# 2_WIZ750SR_Transceiver.net
KiCad netlist of a schematic drawn in Altium Designer
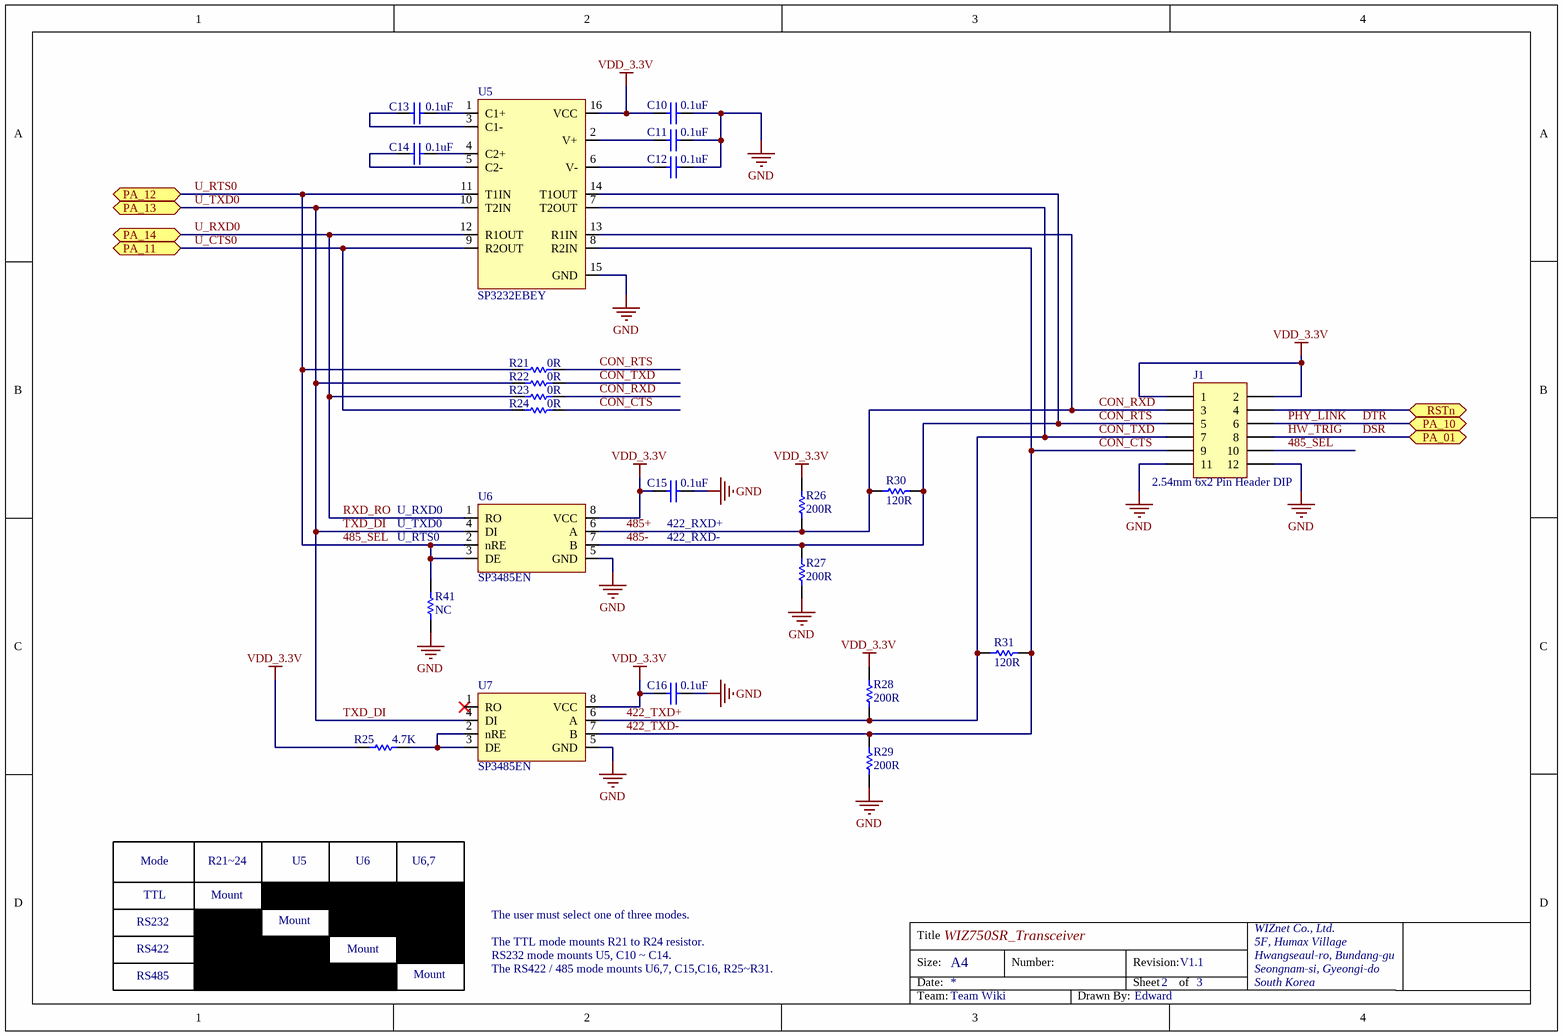
[diagram p0: 2.WIZ750SR_Transceiver.SchDoc]

(export (version "E")
  (design (tool "Eeschema 10.0.6"))
  (components
    (comp (ref "C10")
      (value "0.1uF")
      (footprint "CAP-0402")
      (description "Ceramic CAP 0402(1005)")
      (libsource (lib "Scott_lib") (part "CAP-0402"))
    )
    (comp (ref "C11")
      (value "0.1uF")
      (footprint "CAP-0402")
      (description "Ceramic CAP 0402(1005)")
      (libsource (lib "Scott_lib") (part "CAP-0402"))
    )
    (comp (ref "C12")
      (value "0.1uF")
      (footprint "CAP-0402")
      (description "Ceramic CAP 0402(1005)")
      (libsource (lib "Scott_lib") (part "CAP-0402"))
    )
    (comp (ref "C13")
      (value "0.1uF")
      (footprint "CAP-0402")
      (description "Ceramic CAP 0402(1005)")
      (libsource (lib "Scott_lib") (part "CAP-0402"))
    )
    (comp (ref "C14")
      (value "0.1uF")
      (footprint "CAP-0402")
      (description "Ceramic CAP 0402(1005)")
      (libsource (lib "Scott_lib") (part "CAP-0402"))
    )
    (comp (ref "C15")
      (value "0.1uF")
      (footprint "CAP-0402")
      (description "Ceramic CAP 0402(1005)")
      (libsource (lib "Scott_lib") (part "CAP-0402"))
    )
    (comp (ref "C16")
      (value "0.1uF")
      (footprint "CAP-0402")
      (description "Ceramic CAP 0402(1005)")
      (libsource (lib "Scott_lib") (part "CAP-0402"))
    )
    (comp (ref "J1")
      (value "2.54mm 6x2 Pin Header DIP")
      (footprint "IDC-2X6")
      (description "Header, 6-Pin, Dual row")
      (fields (field (name "PUBLISHER") "Altium Limited"))
      (libsource (lib "Miscellaneous Connectors") (part "Header 6X2"))
    )
    (comp (ref "R21")
      (value "0R")
      (footprint "RES-0402")
      (description "RES-0402")
      (libsource (lib "Scott_lib") (part "RES-0402"))
    )
    (comp (ref "R22")
      (value "0R")
      (footprint "RES-0402")
      (description "RES-0402")
      (libsource (lib "Scott_lib") (part "RES-0402"))
    )
    (comp (ref "R23")
      (value "0R")
      (footprint "RES-0402")
      (description "RES-0402")
      (libsource (lib "Scott_lib") (part "RES-0402"))
    )
    (comp (ref "R24")
      (value "0R")
      (footprint "RES-0402")
      (description "RES-0402")
      (libsource (lib "Scott_lib") (part "RES-0402"))
    )
    (comp (ref "R25")
      (value "4.7K")
      (footprint "RES-0402")
      (description "RES-0402")
      (libsource (lib "Scott_lib") (part "RES-0402"))
    )
    (comp (ref "R26")
      (value "200R")
      (footprint "RES-0402")
      (description "RES-0402")
      (libsource (lib "Scott_lib") (part "RES-0402"))
    )
    (comp (ref "R27")
      (value "200R")
      (footprint "RES-0402")
      (description "RES-0402")
      (libsource (lib "Scott_lib") (part "RES-0402"))
    )
    (comp (ref "R28")
      (value "200R")
      (footprint "RES-0402")
      (description "RES-0402")
      (libsource (lib "Scott_lib") (part "RES-0402"))
    )
    (comp (ref "R29")
      (value "200R")
      (footprint "RES-0402")
      (description "RES-0402")
      (libsource (lib "Scott_lib") (part "RES-0402"))
    )
    (comp (ref "R30")
      (value "120R")
      (footprint "RES-0402")
      (description "RES-0402")
      (libsource (lib "Scott_lib") (part "RES-0402"))
    )
    (comp (ref "R31")
      (value "120R")
      (footprint "RES-0402")
      (description "RES-0402")
      (libsource (lib "Scott_lib") (part "RES-0402"))
    )
    (comp (ref "R41")
      (value "NC")
      (footprint "RES-0402")
      (description "RES-0402")
      (libsource (lib "Scott_lib") (part "RES-0402"))
    )
    (comp (ref "U5")
      (value "SP3232EBEY")
      (footprint "TSSOP16(0.65/6.4)")
      (description "True +3.0V to +5.5V RS-232 Transceivers TSSOP16")
      (libsource (lib "Scott_lib") (part "SP3232EBEY"))
    )
    (comp (ref "U6")
      (value "SP3485EN")
      (footprint "SO-08")
      (description "RS485 Transceiver")
      (libsource (lib "Edward") (part "SP3485EN"))
    )
    (comp (ref "U7")
      (value "SP3485EN")
      (footprint "SO-08")
      (description "RS485 Transceiver")
      (libsource (lib "Edward") (part "SP3485EN"))
    )
  )
  (nets
    (net (code "1") (name "/422_TXD+") (class "Default")
      (node (ref "J1") (pin "7") (pinfunction "7_7") (pintype "passive"))
      (node (ref "R22") (pin "1") (pinfunction "1_1") (pintype "passive"))
      (node (ref "R28") (pin "2") (pinfunction "2_2") (pintype "passive"))
      (node (ref "R31") (pin "2") (pinfunction "2_2") (pintype "passive"))
      (node (ref "U5") (pin "7") (pinfunction "T2OUT_7") (pintype "passive"))
      (node (ref "U7") (pin "6") (pinfunction "A_6") (pintype "passive"))
    )
    (net (code "2") (name "/422_TXD-") (class "Default")
      (node (ref "J1") (pin "9") (pinfunction "9_9") (pintype "passive"))
      (node (ref "R24") (pin "1") (pinfunction "1_1") (pintype "passive"))
      (node (ref "R29") (pin "1") (pinfunction "1_1") (pintype "passive"))
      (node (ref "R31") (pin "1") (pinfunction "1_1") (pintype "passive"))
      (node (ref "U5") (pin "8") (pinfunction "R2IN_8") (pintype "passive"))
      (node (ref "U7") (pin "7") (pinfunction "B_7") (pintype "passive"))
    )
    (net (code "3") (name "/485+") (class "Default")
      (node (ref "J1") (pin "3") (pinfunction "3_3") (pintype "passive"))
      (node (ref "R23") (pin "1") (pinfunction "1_1") (pintype "passive"))
      (node (ref "R26") (pin "2") (pinfunction "2_2") (pintype "passive"))
      (node (ref "R30") (pin "2") (pinfunction "2_2") (pintype "passive"))
      (node (ref "U5") (pin "13") (pinfunction "R1IN_13") (pintype "passive"))
      (node (ref "U6") (pin "6") (pinfunction "A_6") (pintype "passive"))
    )
    (net (code "4") (name "/485-") (class "Default")
      (node (ref "J1") (pin "5") (pinfunction "5_5") (pintype "passive"))
      (node (ref "R21") (pin "1") (pinfunction "1_1") (pintype "passive"))
      (node (ref "R27") (pin "1") (pinfunction "1_1") (pintype "passive"))
      (node (ref "R30") (pin "1") (pinfunction "1_1") (pintype "passive"))
      (node (ref "U5") (pin "14") (pinfunction "T1OUT_14") (pintype "passive"))
      (node (ref "U6") (pin "7") (pinfunction "B_7") (pintype "passive"))
    )
    (net (code "5") (name "/485_SEL") (class "Default")
      (node (ref "J1") (pin "10") (pinfunction "10_10") (pintype "passive"))
      (node (ref "R21") (pin "2") (pinfunction "2_2") (pintype "passive"))
      (node (ref "R41") (pin "1") (pinfunction "1_1") (pintype "passive"))
      (node (ref "U5") (pin "11") (pinfunction "T1IN_11") (pintype "passive"))
      (node (ref "U6") (pin "2") (pinfunction "nRE_2") (pintype "passive"))
      (node (ref "U6") (pin "3") (pinfunction "DE_3") (pintype "passive"))
    )
    (net (code "6") (name "/DSR") (class "Default")
      (node (ref "J1") (pin "8") (pinfunction "8_8") (pintype "passive"))
    )
    (net (code "7") (name "/DTR") (class "Default")
      (node (ref "J1") (pin "6") (pinfunction "6_6") (pintype "passive"))
    )
    (net (code "8") (name "/RSTn") (class "Default")
      (node (ref "J1") (pin "4") (pinfunction "4_4") (pintype "passive"))
    )
    (net (code "9") (name "/RXD_RO") (class "Default")
      (node (ref "R23") (pin "2") (pinfunction "2_2") (pintype "passive"))
      (node (ref "U5") (pin "12") (pinfunction "R1OUT_12") (pintype "passive"))
      (node (ref "U6") (pin "1") (pinfunction "RO_1") (pintype "passive"))
    )
    (net (code "10") (name "/TXD_DI") (class "Default")
      (node (ref "R22") (pin "2") (pinfunction "2_2") (pintype "passive"))
      (node (ref "U5") (pin "10") (pinfunction "T2IN_10") (pintype "passive"))
      (node (ref "U6") (pin "4") (pinfunction "DI_4") (pintype "passive"))
      (node (ref "U7") (pin "4") (pinfunction "DI_4") (pintype "passive"))
    )
    (net (code "11") (name "/U_CTS0") (class "Default")
      (node (ref "R24") (pin "2") (pinfunction "2_2") (pintype "passive"))
      (node (ref "U5") (pin "9") (pinfunction "R2OUT_9") (pintype "passive"))
    )
    (net (code "12") (name "GND") (class "Default")
      (node (ref "C10") (pin "1") (pinfunction "1_1") (pintype "passive"))
      (node (ref "C11") (pin "1") (pinfunction "1_1") (pintype "passive"))
      (node (ref "C12") (pin "1") (pinfunction "1_1") (pintype "passive"))
      (node (ref "C15") (pin "1") (pinfunction "1_1") (pintype "passive"))
      (node (ref "C16") (pin "1") (pinfunction "1_1") (pintype "passive"))
      (node (ref "J1") (pin "11") (pinfunction "11_11") (pintype "passive"))
      (node (ref "J1") (pin "12") (pinfunction "12_12") (pintype "passive"))
      (node (ref "R27") (pin "2") (pinfunction "2_2") (pintype "passive"))
      (node (ref "R29") (pin "2") (pinfunction "2_2") (pintype "passive"))
      (node (ref "R41") (pin "2") (pinfunction "2_2") (pintype "passive"))
      (node (ref "U5") (pin "15") (pinfunction "GND_15") (pintype "passive"))
      (node (ref "U6") (pin "5") (pinfunction "GND_5") (pintype "passive"))
      (node (ref "U7") (pin "5") (pinfunction "GND_5") (pintype "passive"))
    )
    (net (code "13") (name "Net-(U5-C1+)") (class "Default")
      (node (ref "C13") (pin "1") (pinfunction "1_1") (pintype "passive"))
      (node (ref "U5") (pin "1") (pinfunction "C1+_1") (pintype "passive"))
    )
    (net (code "14") (name "Net-(U5-C1-)") (class "Default")
      (node (ref "C13") (pin "2") (pinfunction "2_2") (pintype "passive"))
      (node (ref "U5") (pin "3") (pinfunction "C1-_3") (pintype "passive"))
    )
    (net (code "15") (name "Net-(U5-C2+)") (class "Default")
      (node (ref "C14") (pin "1") (pinfunction "1_1") (pintype "passive"))
      (node (ref "U5") (pin "4") (pinfunction "C2+_4") (pintype "passive"))
    )
    (net (code "16") (name "Net-(U5-C2-)") (class "Default")
      (node (ref "C14") (pin "2") (pinfunction "2_2") (pintype "passive"))
      (node (ref "U5") (pin "5") (pinfunction "C2-_5") (pintype "passive"))
    )
    (net (code "17") (name "Net-(U5-V+)") (class "Default")
      (node (ref "C11") (pin "2") (pinfunction "2_2") (pintype "passive"))
      (node (ref "U5") (pin "2") (pinfunction "V+_2") (pintype "passive"))
    )
    (net (code "18") (name "Net-(U5-V-)") (class "Default")
      (node (ref "C12") (pin "2") (pinfunction "2_2") (pintype "passive"))
      (node (ref "U5") (pin "6") (pinfunction "V-_6") (pintype "passive"))
    )
    (net (code "19") (name "Net-(U7-DE)") (class "Default")
      (node (ref "R25") (pin "1") (pinfunction "1_1") (pintype "passive"))
      (node (ref "U7") (pin "2") (pinfunction "nRE_2") (pintype "passive"))
      (node (ref "U7") (pin "3") (pinfunction "DE_3") (pintype "passive"))
    )
    (net (code "20") (name "VDD_3.3V") (class "Default")
      (node (ref "C10") (pin "2") (pinfunction "2_2") (pintype "passive"))
      (node (ref "C15") (pin "2") (pinfunction "2_2") (pintype "passive"))
      (node (ref "C16") (pin "2") (pinfunction "2_2") (pintype "passive"))
      (node (ref "J1") (pin "1") (pinfunction "1_1") (pintype "passive"))
      (node (ref "J1") (pin "2") (pinfunction "2_2") (pintype "passive"))
      (node (ref "R25") (pin "2") (pinfunction "2_2") (pintype "passive"))
      (node (ref "R26") (pin "1") (pinfunction "1_1") (pintype "passive"))
      (node (ref "R28") (pin "1") (pinfunction "1_1") (pintype "passive"))
      (node (ref "U5") (pin "16") (pinfunction "VCC_16") (pintype "passive"))
      (node (ref "U6") (pin "8") (pinfunction "VCC_8") (pintype "passive"))
      (node (ref "U7") (pin "8") (pinfunction "VCC_8") (pintype "passive"))
    )
    (net (code "21") (name "unconnected-(U7-RO-Pad1)") (class "Default")
      (node (ref "U7") (pin "1") (pinfunction "RO_1") (pintype "passive+no_connect"))
    )
  )
)
